# 4_cpu_control.net
KiCad netlist of a schematic drawn in EAGLE
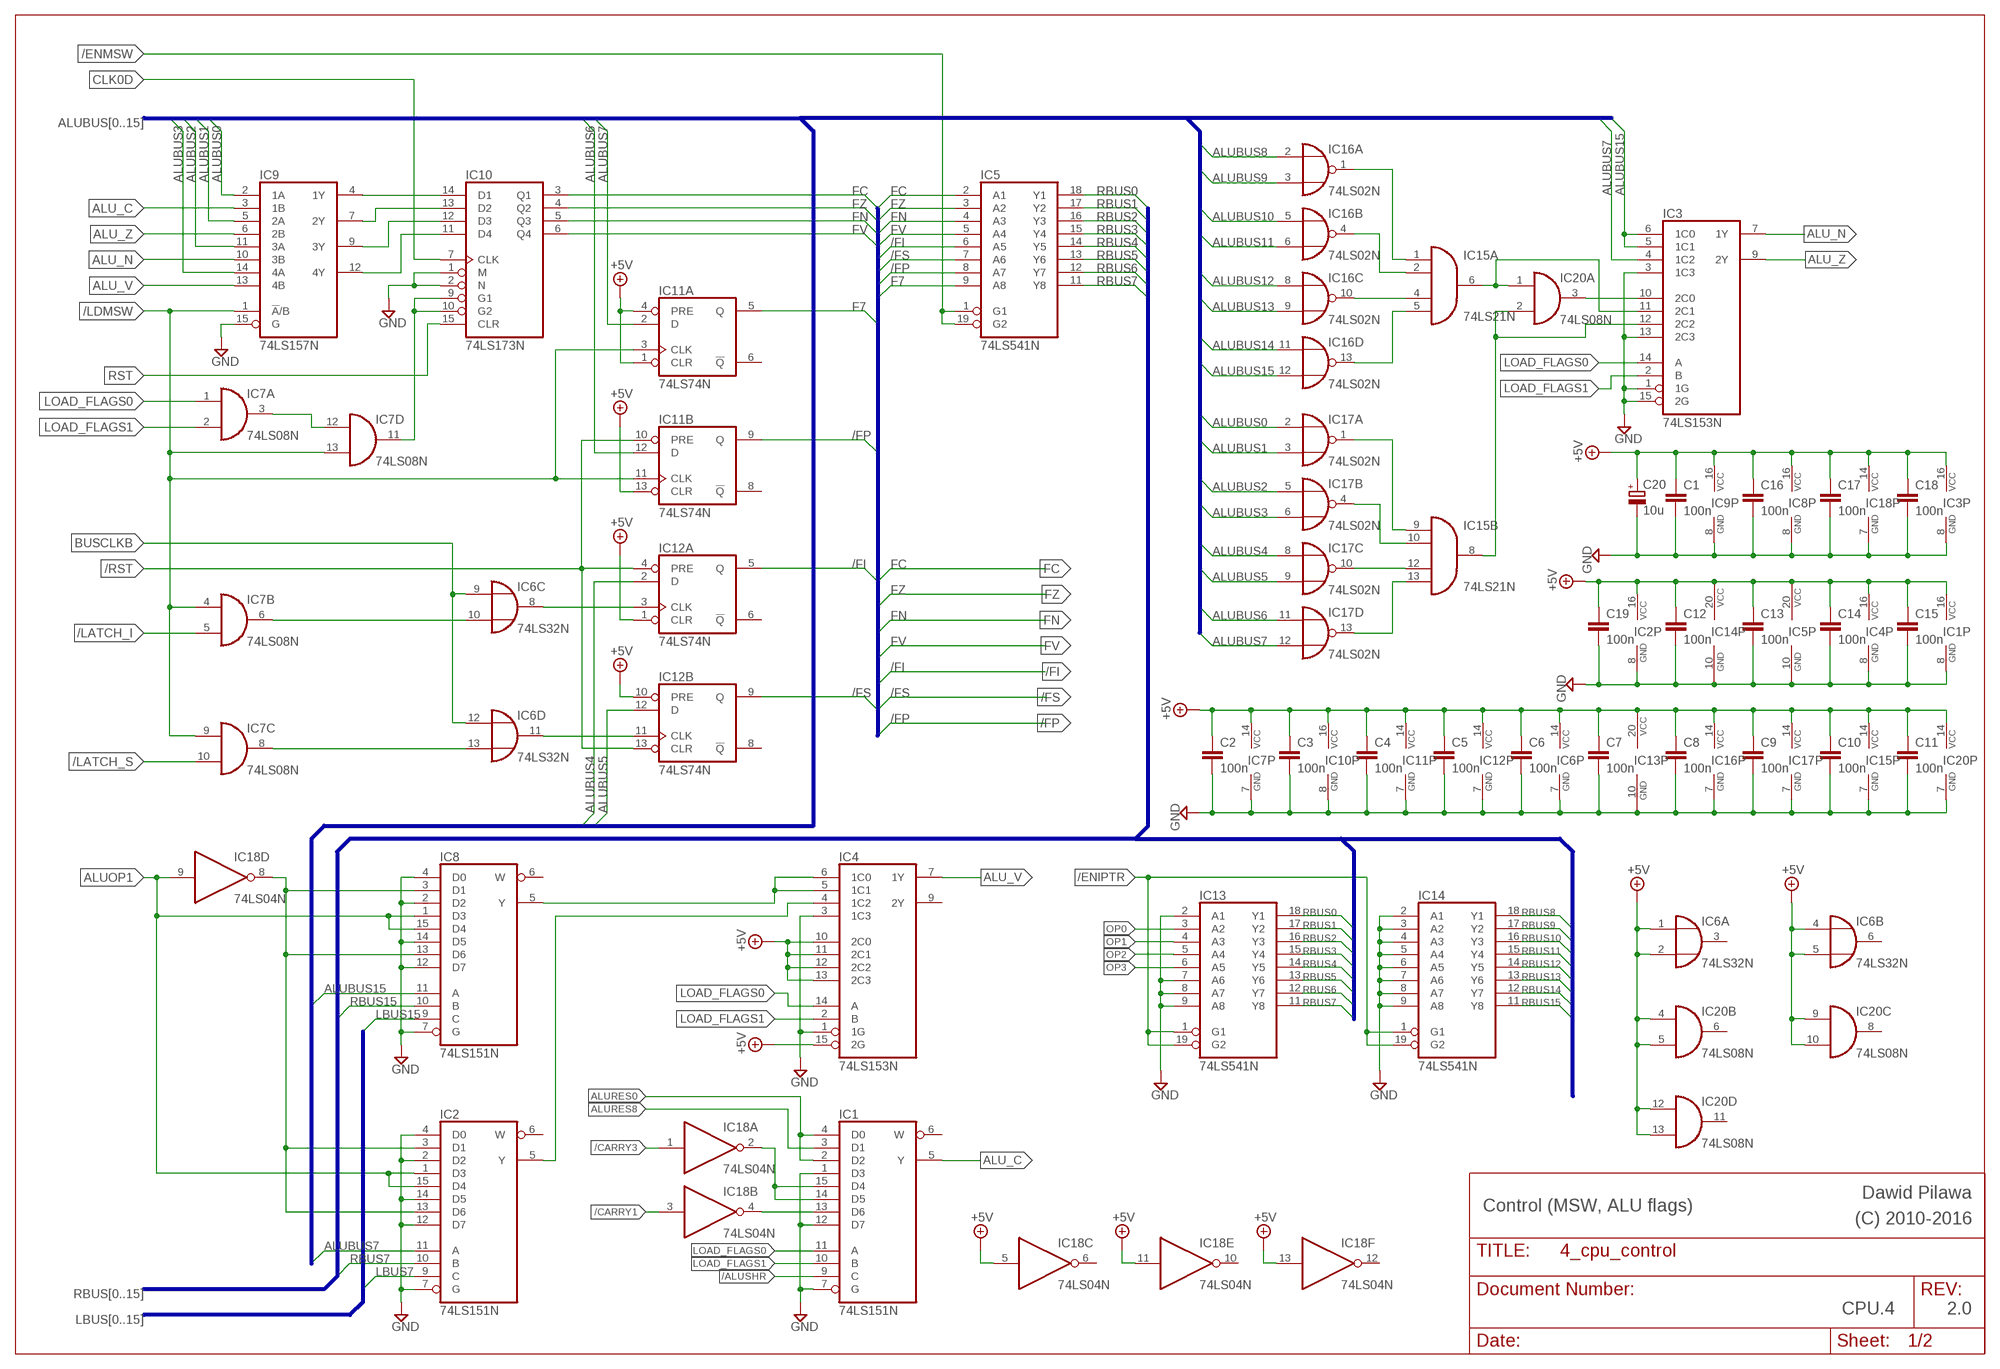
[diagram p0: schematic, sheet 1]
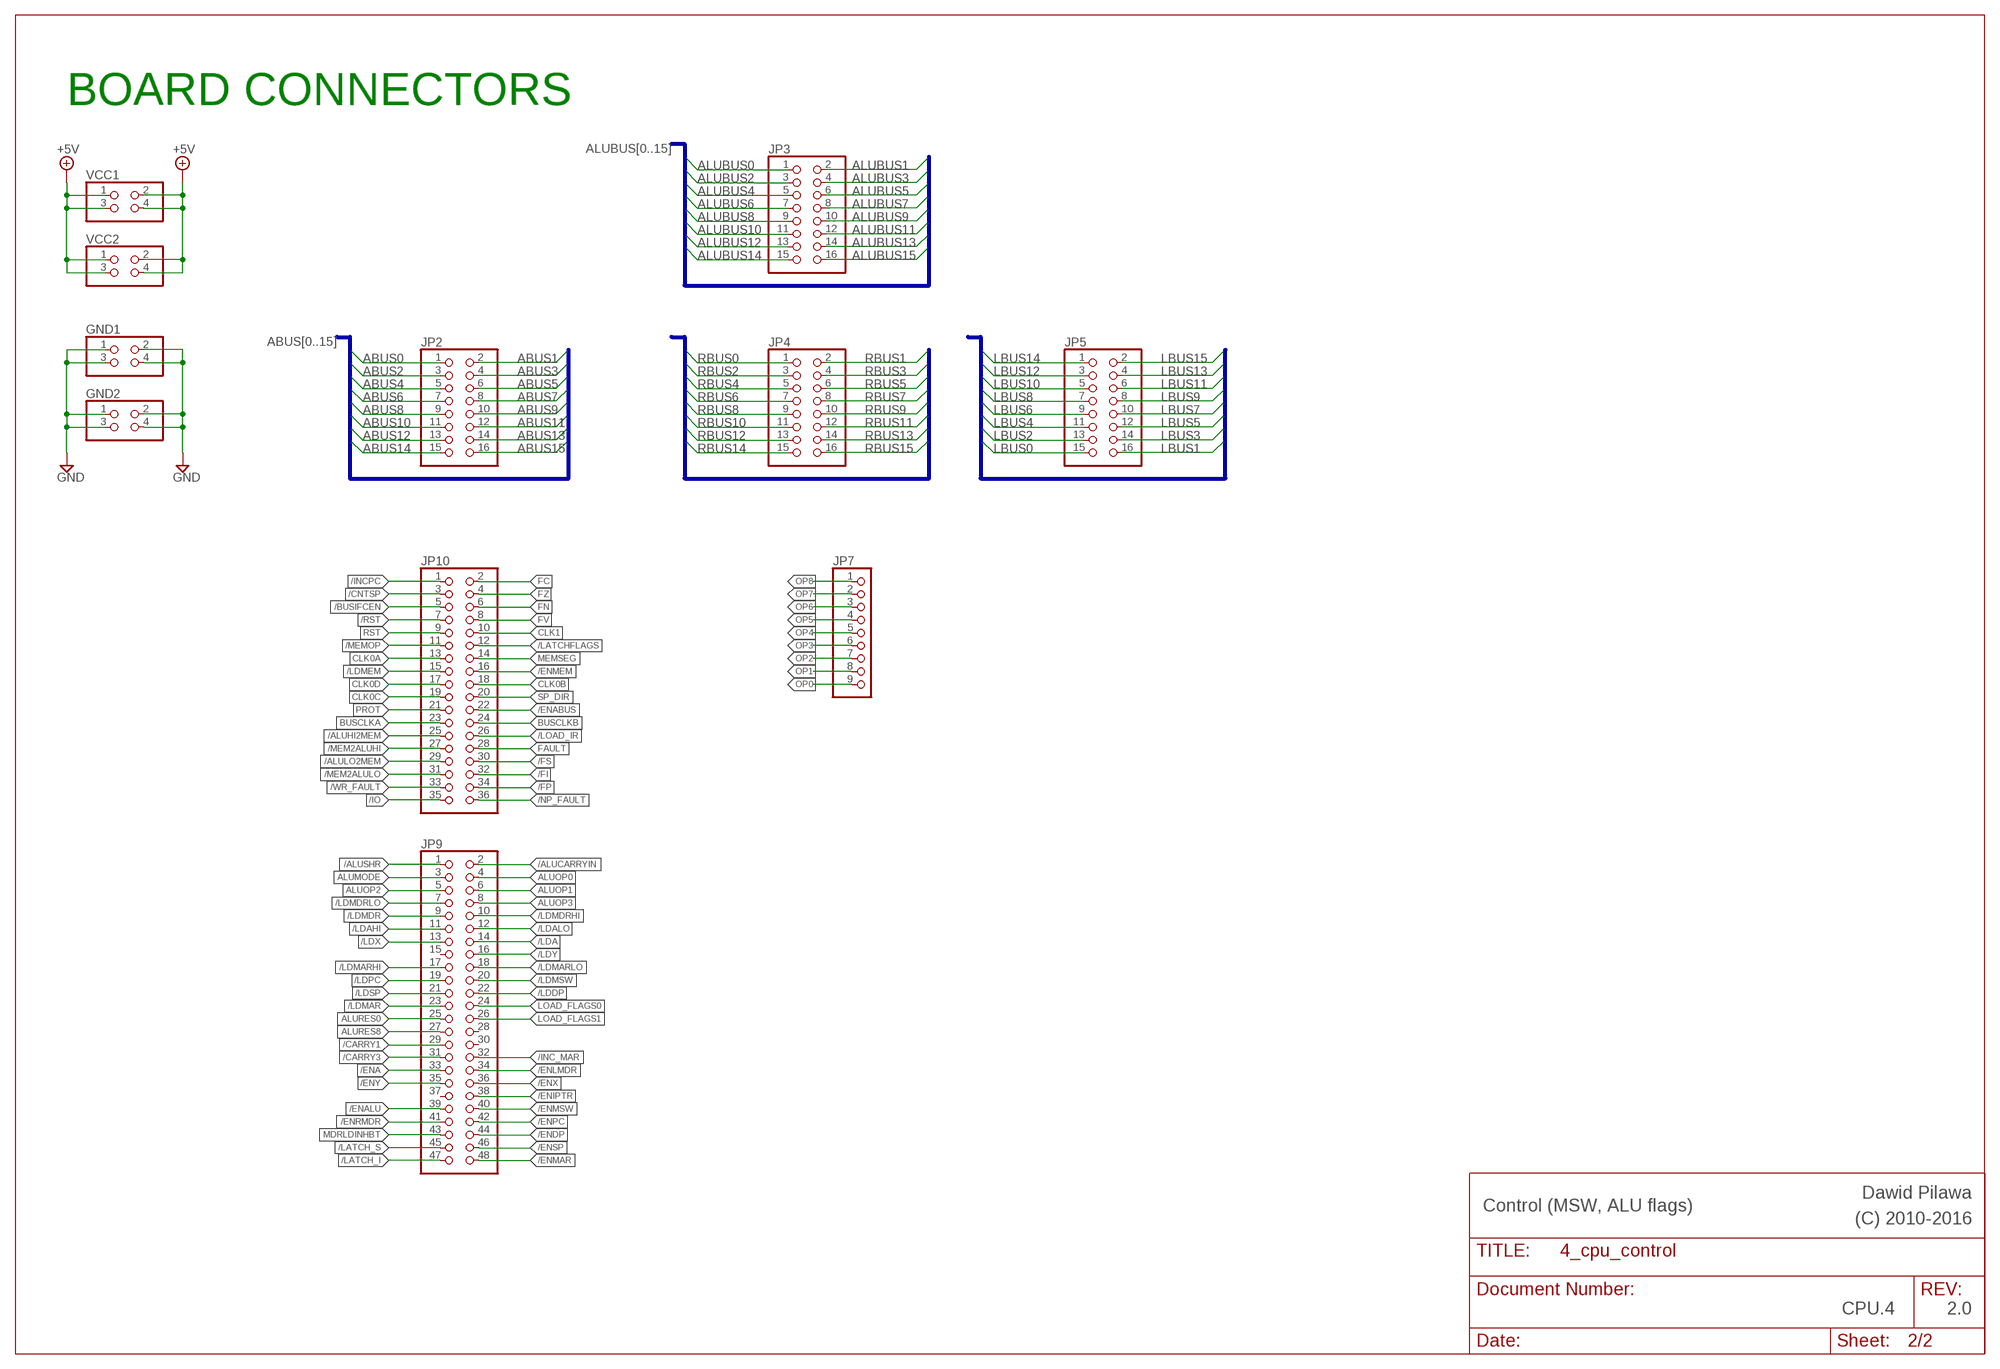
[diagram p1: schematic, sheet 2]

(export (version "E")
  (design (tool "Eeschema 10.0.6"))
  (components
    (comp (ref "GND1")
      (value "PINHD-2X2")
      (footprint "eagle-import:2X02")
      (libsource (lib "eagle-import") (part "PINHD-2X2"))
    )
    (comp (ref "GND2")
      (value "PINHD-2X2")
      (footprint "eagle-import:2X02")
      (libsource (lib "eagle-import") (part "PINHD-2X2"))
    )
    (comp (ref "JP2")
      (value "PINHD-2X8")
      (footprint "eagle-import:2X08")
      (libsource (lib "eagle-import") (part "PINHD-2X8"))
    )
    (comp (ref "JP3")
      (value "PINHD-2X8")
      (footprint "eagle-import:2X08")
      (libsource (lib "eagle-import") (part "PINHD-2X8"))
    )
    (comp (ref "JP4")
      (value "PINHD-2X8")
      (footprint "eagle-import:2X08")
      (libsource (lib "eagle-import") (part "PINHD-2X8"))
    )
    (comp (ref "JP5")
      (value "PINHD-2X8")
      (footprint "eagle-import:2X08")
      (libsource (lib "eagle-import") (part "PINHD-2X8"))
    )
    (comp (ref "JP7")
      (value "PINHD-1X9")
      (footprint "eagle-import:1X09")
      (libsource (lib "eagle-import") (part "PINHD-1X9"))
    )
    (comp (ref "JP9")
      (value "PINHD-2X24")
      (footprint "eagle-import:2X24")
      (libsource (lib "eagle-import") (part "PINHD-2X24"))
    )
    (comp (ref "JP10")
      (value "PINHD-2X18")
      (footprint "eagle-import:2X18")
      (libsource (lib "eagle-import") (part "PINHD-2X18"))
    )
    (comp (ref "VCC1")
      (value "PINHD-2X2")
      (footprint "eagle-import:2X02")
      (libsource (lib "eagle-import") (part "PINHD-2X2"))
    )
    (comp (ref "VCC2")
      (value "PINHD-2X2")
      (footprint "eagle-import:2X02")
      (libsource (lib "eagle-import") (part "PINHD-2X2"))
    )
    (comp (ref "C1")
      (value "100n")
      (footprint "eagle-import:C050-024X044")
      (libsource (lib "eagle-import") (part "C-EU050-024X044"))
    )
    (comp (ref "C2")
      (value "100n")
      (footprint "eagle-import:C050-024X044")
      (libsource (lib "eagle-import") (part "C-EU050-024X044"))
    )
    (comp (ref "C3")
      (value "100n")
      (footprint "eagle-import:C050-024X044")
      (libsource (lib "eagle-import") (part "C-EU050-024X044"))
    )
    (comp (ref "C4")
      (value "100n")
      (footprint "eagle-import:C050-024X044")
      (libsource (lib "eagle-import") (part "C-EU050-024X044"))
    )
    (comp (ref "C5")
      (value "100n")
      (footprint "eagle-import:C050-024X044")
      (libsource (lib "eagle-import") (part "C-EU050-024X044"))
    )
    (comp (ref "C6")
      (value "100n")
      (footprint "eagle-import:C050-024X044")
      (libsource (lib "eagle-import") (part "C-EU050-024X044"))
    )
    (comp (ref "C7")
      (value "100n")
      (footprint "eagle-import:C050-024X044")
      (libsource (lib "eagle-import") (part "C-EU050-024X044"))
    )
    (comp (ref "C8")
      (value "100n")
      (footprint "eagle-import:C050-024X044")
      (libsource (lib "eagle-import") (part "C-EU050-024X044"))
    )
    (comp (ref "C9")
      (value "100n")
      (footprint "eagle-import:C050-024X044")
      (libsource (lib "eagle-import") (part "C-EU050-024X044"))
    )
    (comp (ref "C10")
      (value "100n")
      (footprint "eagle-import:C050-024X044")
      (libsource (lib "eagle-import") (part "C-EU050-024X044"))
    )
    (comp (ref "C11")
      (value "100n")
      (footprint "eagle-import:C050-024X044")
      (libsource (lib "eagle-import") (part "C-EU050-024X044"))
    )
    (comp (ref "C12")
      (value "100n")
      (footprint "eagle-import:C050-024X044")
      (libsource (lib "eagle-import") (part "C-EU050-024X044"))
    )
    (comp (ref "C13")
      (value "100n")
      (footprint "eagle-import:C050-024X044")
      (libsource (lib "eagle-import") (part "C-EU050-024X044"))
    )
    (comp (ref "C14")
      (value "100n")
      (footprint "eagle-import:C050-024X044")
      (libsource (lib "eagle-import") (part "C-EU050-024X044"))
    )
    (comp (ref "C15")
      (value "100n")
      (footprint "eagle-import:C050-024X044")
      (libsource (lib "eagle-import") (part "C-EU050-024X044"))
    )
    (comp (ref "C16")
      (value "100n")
      (footprint "eagle-import:C050-024X044")
      (libsource (lib "eagle-import") (part "C-EU050-024X044"))
    )
    (comp (ref "C17")
      (value "100n")
      (footprint "eagle-import:C050-024X044")
      (libsource (lib "eagle-import") (part "C-EU050-024X044"))
    )
    (comp (ref "C18")
      (value "100n")
      (footprint "eagle-import:C050-024X044")
      (libsource (lib "eagle-import") (part "C-EU050-024X044"))
    )
    (comp (ref "C19")
      (value "100n")
      (footprint "eagle-import:C050-024X044")
      (libsource (lib "eagle-import") (part "C-EU050-024X044"))
    )
    (comp (ref "C20")
      (value "10u")
      (footprint "eagle-import:E2,5-6")
      (libsource (lib "eagle-import") (part "CPOL-EUE2.5-6"))
    )
    (comp (ref "IC1")
      (value "74LS151N")
      (footprint "eagle-import:DIL16")
      (libsource (lib "eagle-import") (part "74151NLS"))
    )
    (comp (ref "IC2")
      (value "74LS151N")
      (footprint "eagle-import:DIL16")
      (libsource (lib "eagle-import") (part "74151NLS"))
    )
    (comp (ref "IC3")
      (value "74LS153N")
      (footprint "eagle-import:DIL16")
      (libsource (lib "eagle-import") (part "74153NLS"))
    )
    (comp (ref "IC4")
      (value "74LS153N")
      (footprint "eagle-import:DIL16")
      (libsource (lib "eagle-import") (part "74153NLS"))
    )
    (comp (ref "IC5")
      (value "74LS541N")
      (footprint "eagle-import:DIL20")
      (libsource (lib "eagle-import") (part "74541NLS"))
    )
    (comp (ref "IC6")
      (value "74LS32N")
      (footprint "eagle-import:DIL14")
      (libsource (lib "eagle-import") (part "7432NLS"))
    )
    (comp (ref "IC7")
      (value "74LS08N")
      (footprint "eagle-import:DIL14")
      (libsource (lib "eagle-import") (part "7408NLS"))
    )
    (comp (ref "IC8")
      (value "74LS151N")
      (footprint "eagle-import:DIL16")
      (libsource (lib "eagle-import") (part "74151NLS"))
    )
    (comp (ref "IC9")
      (value "74LS157N")
      (footprint "eagle-import:DIL16")
      (libsource (lib "eagle-import") (part "74157NLS"))
    )
    (comp (ref "IC10")
      (value "74LS173N")
      (footprint "eagle-import:DIL16")
      (libsource (lib "eagle-import") (part "74173NLS"))
    )
    (comp (ref "IC11")
      (value "74LS74N")
      (footprint "eagle-import:DIL14")
      (libsource (lib "eagle-import") (part "7474NLS"))
    )
    (comp (ref "IC12")
      (value "74LS74N")
      (footprint "eagle-import:DIL14")
      (libsource (lib "eagle-import") (part "7474NLS"))
    )
    (comp (ref "IC13")
      (value "74LS541N")
      (footprint "eagle-import:DIL20")
      (libsource (lib "eagle-import") (part "74541NLS"))
    )
    (comp (ref "IC14")
      (value "74LS541N")
      (footprint "eagle-import:DIL20")
      (libsource (lib "eagle-import") (part "74541NLS"))
    )
    (comp (ref "IC15")
      (value "74LS21N")
      (footprint "eagle-import:DIL14")
      (libsource (lib "eagle-import") (part "7421NLS"))
    )
    (comp (ref "IC16")
      (value "74LS02N")
      (footprint "eagle-import:DIL14")
      (libsource (lib "eagle-import") (part "7402NLS"))
    )
    (comp (ref "IC17")
      (value "74LS02N")
      (footprint "eagle-import:DIL14")
      (libsource (lib "eagle-import") (part "7402NLS"))
    )
    (comp (ref "IC18")
      (value "74LS04N")
      (footprint "eagle-import:DIL14")
      (libsource (lib "eagle-import") (part "7404NLS"))
    )
    (comp (ref "IC20")
      (value "74LS08N")
      (footprint "eagle-import:DIL14")
      (libsource (lib "eagle-import") (part "7408NLS"))
    )
  )
  (nets
    (net (code "15") (name "+5V") (class "Default")
      (node (ref "C1") (pin "1") (pinfunction "1_1") (pintype "passive"))
      (node (ref "C10") (pin "1") (pinfunction "1_1") (pintype "passive"))
      (node (ref "C11") (pin "1") (pinfunction "1_1") (pintype "passive"))
      (node (ref "C12") (pin "1") (pinfunction "1_1") (pintype "passive"))
      (node (ref "C13") (pin "1") (pinfunction "1_1") (pintype "passive"))
      (node (ref "C14") (pin "1") (pinfunction "1_1") (pintype "passive"))
      (node (ref "C15") (pin "1") (pinfunction "1_1") (pintype "passive"))
      (node (ref "C16") (pin "1") (pinfunction "1_1") (pintype "passive"))
      (node (ref "C17") (pin "1") (pinfunction "1_1") (pintype "passive"))
      (node (ref "C18") (pin "1") (pinfunction "1_1") (pintype "passive"))
      (node (ref "C19") (pin "1") (pinfunction "1_1") (pintype "passive"))
      (node (ref "C2") (pin "1") (pinfunction "1_1") (pintype "passive"))
      (node (ref "C20") (pin "+") (pinfunction "+_+") (pintype "passive"))
      (node (ref "C3") (pin "1") (pinfunction "1_1") (pintype "passive"))
      (node (ref "C4") (pin "1") (pinfunction "1_1") (pintype "passive"))
      (node (ref "C5") (pin "1") (pinfunction "1_1") (pintype "passive"))
      (node (ref "C6") (pin "1") (pinfunction "1_1") (pintype "passive"))
      (node (ref "C7") (pin "1") (pinfunction "1_1") (pintype "passive"))
      (node (ref "C8") (pin "1") (pinfunction "1_1") (pintype "passive"))
      (node (ref "C9") (pin "1") (pinfunction "1_1") (pintype "passive"))
      (node (ref "IC1") (pin "16") (pinfunction "VCC_16") (pintype "power_in"))
      (node (ref "IC10") (pin "16") (pinfunction "VCC_16") (pintype "power_in"))
      (node (ref "IC11") (pin "1") (pinfunction "CLR_1") (pintype "input"))
      (node (ref "IC11") (pin "13") (pinfunction "CLR_13") (pintype "input"))
      (node (ref "IC11") (pin "14") (pinfunction "VCC_14") (pintype "power_in"))
      (node (ref "IC11") (pin "4") (pinfunction "PRE_4") (pintype "input"))
      (node (ref "IC12") (pin "1") (pinfunction "CLR_1") (pintype "input"))
      (node (ref "IC12") (pin "10") (pinfunction "PRE_10") (pintype "input"))
      (node (ref "IC12") (pin "14") (pinfunction "VCC_14") (pintype "power_in"))
      (node (ref "IC13") (pin "20") (pinfunction "VCC_20") (pintype "power_in"))
      (node (ref "IC14") (pin "20") (pinfunction "VCC_20") (pintype "power_in"))
      (node (ref "IC15") (pin "14") (pinfunction "VCC_14") (pintype "power_in"))
      (node (ref "IC16") (pin "14") (pinfunction "VCC_14") (pintype "power_in"))
      (node (ref "IC17") (pin "14") (pinfunction "VCC_14") (pintype "power_in"))
      (node (ref "IC18") (pin "11") (pinfunction "I_11") (pintype "input"))
      (node (ref "IC18") (pin "13") (pinfunction "I_13") (pintype "input"))
      (node (ref "IC18") (pin "14") (pinfunction "VCC_14") (pintype "power_in"))
      (node (ref "IC18") (pin "5") (pinfunction "I_5") (pintype "input"))
      (node (ref "IC2") (pin "16") (pinfunction "VCC_16") (pintype "power_in"))
      (node (ref "IC20") (pin "10") (pinfunction "I1_10") (pintype "input"))
      (node (ref "IC20") (pin "12") (pinfunction "I0_12") (pintype "input"))
      (node (ref "IC20") (pin "13") (pinfunction "I1_13") (pintype "input"))
      (node (ref "IC20") (pin "14") (pinfunction "VCC_14") (pintype "power_in"))
      (node (ref "IC20") (pin "4") (pinfunction "I0_4") (pintype "input"))
      (node (ref "IC20") (pin "5") (pinfunction "I1_5") (pintype "input"))
      (node (ref "IC20") (pin "9") (pinfunction "I0_9") (pintype "input"))
      (node (ref "IC3") (pin "16") (pinfunction "VCC_16") (pintype "power_in"))
      (node (ref "IC4") (pin "10") (pinfunction "2C0_10") (pintype "input"))
      (node (ref "IC4") (pin "11") (pinfunction "2C1_11") (pintype "input"))
      (node (ref "IC4") (pin "12") (pinfunction "2C2_12") (pintype "input"))
      (node (ref "IC4") (pin "13") (pinfunction "2C3_13") (pintype "input"))
      (node (ref "IC4") (pin "15") (pinfunction "2G_15") (pintype "input"))
      (node (ref "IC4") (pin "16") (pinfunction "VCC_16") (pintype "power_in"))
      (node (ref "IC5") (pin "20") (pinfunction "VCC_20") (pintype "power_in"))
      (node (ref "IC6") (pin "1") (pinfunction "I0_1") (pintype "input"))
      (node (ref "IC6") (pin "14") (pinfunction "VCC_14") (pintype "power_in"))
      (node (ref "IC6") (pin "2") (pinfunction "I1_2") (pintype "input"))
      (node (ref "IC6") (pin "4") (pinfunction "I0_4") (pintype "input"))
      (node (ref "IC6") (pin "5") (pinfunction "I1_5") (pintype "input"))
      (node (ref "IC7") (pin "14") (pinfunction "VCC_14") (pintype "power_in"))
      (node (ref "IC8") (pin "16") (pinfunction "VCC_16") (pintype "power_in"))
      (node (ref "IC9") (pin "16") (pinfunction "VCC_16") (pintype "power_in"))
      (node (ref "VCC1") (pin "1") (pinfunction "1_1") (pintype "passive"))
      (node (ref "VCC1") (pin "2") (pinfunction "2_2") (pintype "passive"))
      (node (ref "VCC1") (pin "3") (pinfunction "3_3") (pintype "passive"))
      (node (ref "VCC1") (pin "4") (pinfunction "4_4") (pintype "passive"))
      (node (ref "VCC2") (pin "1") (pinfunction "1_1") (pintype "passive"))
      (node (ref "VCC2") (pin "2") (pinfunction "2_2") (pintype "passive"))
      (node (ref "VCC2") (pin "3") (pinfunction "3_3") (pintype "passive"))
      (node (ref "VCC2") (pin "4") (pinfunction "4_4") (pintype "passive"))
    )
    (net (code "21") (name "ABUS0") (class "Default")
      (node (ref "JP2") (pin "1") (pinfunction "1_1") (pintype "passive"))
    )
    (net (code "22") (name "ABUS1") (class "Default")
      (node (ref "JP2") (pin "2") (pinfunction "2_2") (pintype "passive"))
    )
    (net (code "23") (name "ABUS2") (class "Default")
      (node (ref "JP2") (pin "3") (pinfunction "3_3") (pintype "passive"))
    )
    (net (code "24") (name "ABUS3") (class "Default")
      (node (ref "JP2") (pin "4") (pinfunction "4_4") (pintype "passive"))
    )
    (net (code "25") (name "ABUS4") (class "Default")
      (node (ref "JP2") (pin "5") (pinfunction "5_5") (pintype "passive"))
    )
    (net (code "26") (name "ABUS5") (class "Default")
      (node (ref "JP2") (pin "6") (pinfunction "6_6") (pintype "passive"))
    )
    (net (code "27") (name "ABUS6") (class "Default")
      (node (ref "JP2") (pin "7") (pinfunction "7_7") (pintype "passive"))
    )
    (net (code "28") (name "ABUS7") (class "Default")
      (node (ref "JP2") (pin "8") (pinfunction "8_8") (pintype "passive"))
    )
    (net (code "29") (name "ABUS8") (class "Default")
      (node (ref "JP2") (pin "9") (pinfunction "9_9") (pintype "passive"))
    )
    (net (code "30") (name "ABUS9") (class "Default")
      (node (ref "JP2") (pin "10") (pinfunction "10_10") (pintype "passive"))
    )
    (net (code "31") (name "ABUS10") (class "Default")
      (node (ref "JP2") (pin "11") (pinfunction "11_11") (pintype "passive"))
    )
    (net (code "32") (name "ABUS11") (class "Default")
      (node (ref "JP2") (pin "12") (pinfunction "12_12") (pintype "passive"))
    )
    (net (code "33") (name "ABUS12") (class "Default")
      (node (ref "JP2") (pin "13") (pinfunction "13_13") (pintype "passive"))
    )
    (net (code "34") (name "ABUS13") (class "Default")
      (node (ref "JP2") (pin "14") (pinfunction "14_14") (pintype "passive"))
    )
    (net (code "35") (name "ABUS14") (class "Default")
      (node (ref "JP2") (pin "15") (pinfunction "15_15") (pintype "passive"))
    )
    (net (code "36") (name "ABUS15") (class "Default")
      (node (ref "JP2") (pin "16") (pinfunction "16_16") (pintype "passive"))
    )
    (net (code "37") (name "ALUBUS0") (class "Default")
      (node (ref "IC17") (pin "2") (pinfunction "I0_2") (pintype "input"))
      (node (ref "IC9") (pin "2") (pinfunction "1A_2") (pintype "input"))
      (node (ref "JP3") (pin "1") (pinfunction "1_1") (pintype "passive"))
    )
    (net (code "38") (name "ALUBUS1") (class "Default")
      (node (ref "IC17") (pin "3") (pinfunction "I1_3") (pintype "input"))
      (node (ref "IC9") (pin "5") (pinfunction "2A_5") (pintype "input"))
      (node (ref "JP3") (pin "2") (pinfunction "2_2") (pintype "passive"))
    )
    (net (code "39") (name "ALUBUS2") (class "Default")
      (node (ref "IC17") (pin "5") (pinfunction "I0_5") (pintype "input"))
      (node (ref "IC9") (pin "11") (pinfunction "3A_11") (pintype "input"))
      (node (ref "JP3") (pin "3") (pinfunction "3_3") (pintype "passive"))
    )
    (net (code "40") (name "ALUBUS3") (class "Default")
      (node (ref "IC17") (pin "6") (pinfunction "I1_6") (pintype "input"))
      (node (ref "IC9") (pin "14") (pinfunction "4A_14") (pintype "input"))
      (node (ref "JP3") (pin "4") (pinfunction "4_4") (pintype "passive"))
    )
    (net (code "41") (name "ALUBUS4") (class "Default")
      (node (ref "IC12") (pin "2") (pinfunction "D_2") (pintype "input"))
      (node (ref "IC17") (pin "8") (pinfunction "I0_8") (pintype "input"))
      (node (ref "JP3") (pin "5") (pinfunction "5_5") (pintype "passive"))
    )
    (net (code "42") (name "ALUBUS5") (class "Default")
      (node (ref "IC12") (pin "12") (pinfunction "D_12") (pintype "input"))
      (node (ref "IC17") (pin "9") (pinfunction "I1_9") (pintype "input"))
      (node (ref "JP3") (pin "6") (pinfunction "6_6") (pintype "passive"))
    )
    (net (code "43") (name "ALUBUS6") (class "Default")
      (node (ref "IC11") (pin "12") (pinfunction "D_12") (pintype "input"))
      (node (ref "IC17") (pin "11") (pinfunction "I0_11") (pintype "input"))
      (node (ref "JP3") (pin "7") (pinfunction "7_7") (pintype "passive"))
    )
    (net (code "44") (name "ALUBUS7") (class "Default")
      (node (ref "IC11") (pin "2") (pinfunction "D_2") (pintype "input"))
      (node (ref "IC17") (pin "12") (pinfunction "I1_12") (pintype "input"))
      (node (ref "IC2") (pin "11") (pinfunction "A_11") (pintype "input"))
      (node (ref "IC3") (pin "4") (pinfunction "1C2_4") (pintype "input"))
      (node (ref "JP3") (pin "8") (pinfunction "8_8") (pintype "passive"))
    )
    (net (code "45") (name "ALUBUS8") (class "Default")
      (node (ref "IC16") (pin "2") (pinfunction "I0_2") (pintype "input"))
      (node (ref "JP3") (pin "9") (pinfunction "9_9") (pintype "passive"))
    )
    (net (code "46") (name "ALUBUS9") (class "Default")
      (node (ref "IC16") (pin "3") (pinfunction "I1_3") (pintype "input"))
      (node (ref "JP3") (pin "10") (pinfunction "10_10") (pintype "passive"))
    )
    (net (code "47") (name "ALUBUS10") (class "Default")
      (node (ref "IC16") (pin "5") (pinfunction "I0_5") (pintype "input"))
      (node (ref "JP3") (pin "11") (pinfunction "11_11") (pintype "passive"))
    )
    (net (code "48") (name "ALUBUS11") (class "Default")
      (node (ref "IC16") (pin "6") (pinfunction "I1_6") (pintype "input"))
      (node (ref "JP3") (pin "12") (pinfunction "12_12") (pintype "passive"))
    )
    (net (code "49") (name "ALUBUS12") (class "Default")
      (node (ref "IC16") (pin "8") (pinfunction "I0_8") (pintype "input"))
      (node (ref "JP3") (pin "13") (pinfunction "13_13") (pintype "passive"))
    )
    (net (code "50") (name "ALUBUS13") (class "Default")
      (node (ref "IC16") (pin "9") (pinfunction "I1_9") (pintype "input"))
      (node (ref "JP3") (pin "14") (pinfunction "14_14") (pintype "passive"))
    )
    (net (code "51") (name "ALUBUS14") (class "Default")
      (node (ref "IC16") (pin "11") (pinfunction "I0_11") (pintype "input"))
      (node (ref "JP3") (pin "15") (pinfunction "15_15") (pintype "passive"))
    )
    (net (code "52") (name "ALUBUS15") (class "Default")
      (node (ref "IC16") (pin "12") (pinfunction "I1_12") (pintype "input"))
      (node (ref "IC3") (pin "5") (pinfunction "1C1_5") (pintype "input"))
      (node (ref "IC3") (pin "6") (pinfunction "1C0_6") (pintype "input"))
      (node (ref "IC8") (pin "11") (pinfunction "A_11") (pintype "input"))
      (node (ref "JP3") (pin "16") (pinfunction "16_16") (pintype "passive"))
    )
    (net (code "53") (name "ALUMODE") (class "Default")
      (node (ref "JP9") (pin "3") (pinfunction "3_3") (pintype "passive"))
    )
    (net (code "54") (name "ALUOP0") (class "Default")
      (node (ref "JP9") (pin "4") (pinfunction "4_4") (pintype "passive"))
    )
    (net (code "55") (name "ALUOP1") (class "Default")
      (node (ref "IC18") (pin "9") (pinfunction "I_9") (pintype "input"))
      (node (ref "IC2") (pin "1") (pinfunction "D3_1") (pintype "input"))
      (node (ref "IC2") (pin "15") (pinfunction "D4_15") (pintype "input"))
      (node (ref "IC8") (pin "1") (pinfunction "D3_1") (pintype "input"))
      (node (ref "IC8") (pin "15") (pinfunction "D4_15") (pintype "input"))
      (node (ref "JP9") (pin "6") (pinfunction "6_6") (pintype "passive"))
    )
    (net (code "56") (name "ALUOP2") (class "Default")
      (node (ref "JP9") (pin "5") (pinfunction "5_5") (pintype "passive"))
    )
    (net (code "57") (name "ALUOP3") (class "Default")
      (node (ref "JP9") (pin "8") (pinfunction "8_8") (pintype "passive"))
    )
    (net (code "58") (name "ALURES0") (class "Default")
      (node (ref "IC1") (pin "2") (pinfunction "D2_2") (pintype "input"))
      (node (ref "IC1") (pin "4") (pinfunction "D0_4") (pintype "input"))
      (node (ref "JP9") (pin "25") (pinfunction "25_25") (pintype "passive"))
    )
    (net (code "59") (name "ALURES8") (class "Default")
      (node (ref "IC1") (pin "3") (pinfunction "D1_3") (pintype "input"))
      (node (ref "JP9") (pin "27") (pinfunction "27_27") (pintype "passive"))
    )
    (net (code "60") (name "ALU_C") (class "Default")
      (node (ref "IC1") (pin "5") (pinfunction "Y_5") (pintype "output"))
      (node (ref "IC9") (pin "3") (pinfunction "1B_3") (pintype "input"))
    )
    (net (code "61") (name "ALU_N") (class "Default")
      (node (ref "IC3") (pin "7") (pinfunction "1Y_7") (pintype "output"))
      (node (ref "IC9") (pin "10") (pinfunction "3B_10") (pintype "input"))
    )
    (net (code "62") (name "ALU_V") (class "Default")
      (node (ref "IC4") (pin "7") (pinfunction "1Y_7") (pintype "output"))
      (node (ref "IC9") (pin "13") (pinfunction "4B_13") (pintype "input"))
    )
    (net (code "63") (name "ALU_Z") (class "Default")
      (node (ref "IC3") (pin "9") (pinfunction "2Y_9") (pintype "output"))
      (node (ref "IC9") (pin "6") (pinfunction "2B_6") (pintype "input"))
    )
    (net (code "64") (name "BUSCLKA") (class "Default")
      (node (ref "JP10") (pin "23") (pinfunction "23_23") (pintype "passive"))
    )
    (net (code "65") (name "BUSCLKB") (class "Default")
      (node (ref "IC6") (pin "12") (pinfunction "I0_12") (pintype "input"))
      (node (ref "IC6") (pin "9") (pinfunction "I0_9") (pintype "input"))
      (node (ref "JP10") (pin "24") (pinfunction "24_24") (pintype "passive"))
    )
    (net (code "66") (name "CLK0A") (class "Default")
      (node (ref "JP10") (pin "13") (pinfunction "13_13") (pintype "passive"))
    )
    (net (code "67") (name "CLK0B") (class "Default")
      (node (ref "JP10") (pin "18") (pinfunction "18_18") (pintype "passive"))
    )
    (net (code "68") (name "CLK0C") (class "Default")
      (node (ref "JP10") (pin "19") (pinfunction "19_19") (pintype "passive"))
    )
    (net (code "69") (name "CLK0D") (class "Default")
      (node (ref "IC10") (pin "7") (pinfunction "CLK_7") (pintype "input"))
      (node (ref "JP10") (pin "17") (pinfunction "17_17") (pintype "passive"))
    )
    (net (code "70") (name "CLK1") (class "Default")
      (node (ref "JP10") (pin "10") (pinfunction "10_10") (pintype "passive"))
    )
    (net (code "71") (name "F7") (class "Default")
      (node (ref "IC11") (pin "5") (pinfunction "Q_5") (pintype "output"))
      (node (ref "IC5") (pin "9") (pinfunction "A8_9") (pintype "input"))
    )
    (net (code "72") (name "FAULT") (class "Default")
      (node (ref "JP10") (pin "28") (pinfunction "28_28") (pintype "passive"))
    )
    (net (code "73") (name "FC") (class "Default")
      (node (ref "IC10") (pin "3") (pinfunction "Q1_3") (pintype "tri_state"))
      (node (ref "IC5") (pin "2") (pinfunction "A1_2") (pintype "input"))
      (node (ref "JP10") (pin "2") (pinfunction "2_2") (pintype "passive"))
    )
    (net (code "74") (name "FN") (class "Default")
      (node (ref "IC10") (pin "5") (pinfunction "Q3_5") (pintype "tri_state"))
      (node (ref "IC5") (pin "4") (pinfunction "A3_4") (pintype "input"))
      (node (ref "JP10") (pin "6") (pinfunction "6_6") (pintype "passive"))
    )
    (net (code "75") (name "FV") (class "Default")
      (node (ref "IC10") (pin "6") (pinfunction "Q4_6") (pintype "tri_state"))
      (node (ref "IC5") (pin "5") (pinfunction "A4_5") (pintype "input"))
      (node (ref "JP10") (pin "8") (pinfunction "8_8") (pintype "passive"))
    )
    (net (code "76") (name "FZ") (class "Default")
      (node (ref "IC10") (pin "4") (pinfunction "Q2_4") (pintype "tri_state"))
      (node (ref "IC5") (pin "3") (pinfunction "A2_3") (pintype "input"))
      (node (ref "JP10") (pin "4") (pinfunction "4_4") (pintype "passive"))
    )
    (net (code "77") (name "GND") (class "Default")
      (node (ref "C1") (pin "2") (pinfunction "2_2") (pintype "passive"))
      (node (ref "C10") (pin "2") (pinfunction "2_2") (pintype "passive"))
      (node (ref "C11") (pin "2") (pinfunction "2_2") (pintype "passive"))
      (node (ref "C12") (pin "2") (pinfunction "2_2") (pintype "passive"))
      (node (ref "C13") (pin "2") (pinfunction "2_2") (pintype "passive"))
      (node (ref "C14") (pin "2") (pinfunction "2_2") (pintype "passive"))
      (node (ref "C15") (pin "2") (pinfunction "2_2") (pintype "passive"))
      (node (ref "C16") (pin "2") (pinfunction "2_2") (pintype "passive"))
      (node (ref "C17") (pin "2") (pinfunction "2_2") (pintype "passive"))
      (node (ref "C18") (pin "2") (pinfunction "2_2") (pintype "passive"))
      (node (ref "C19") (pin "2") (pinfunction "2_2") (pintype "passive"))
      (node (ref "C2") (pin "2") (pinfunction "2_2") (pintype "passive"))
      (node (ref "C20") (pin "-") (pinfunction "-_-") (pintype "passive"))
      (node (ref "C3") (pin "2") (pinfunction "2_2") (pintype "passive"))
      (node (ref "C4") (pin "2") (pinfunction "2_2") (pintype "passive"))
      (node (ref "C5") (pin "2") (pinfunction "2_2") (pintype "passive"))
      (node (ref "C6") (pin "2") (pinfunction "2_2") (pintype "passive"))
      (node (ref "C7") (pin "2") (pinfunction "2_2") (pintype "passive"))
      (node (ref "C8") (pin "2") (pinfunction "2_2") (pintype "passive"))
      (node (ref "C9") (pin "2") (pinfunction "2_2") (pintype "passive"))
      (node (ref "GND1") (pin "1") (pinfunction "1_1") (pintype "passive"))
      (node (ref "GND1") (pin "2") (pinfunction "2_2") (pintype "passive"))
      (node (ref "GND1") (pin "3") (pinfunction "3_3") (pintype "passive"))
      (node (ref "GND1") (pin "4") (pinfunction "4_4") (pintype "passive"))
      (node (ref "GND2") (pin "1") (pinfunction "1_1") (pintype "passive"))
      (node (ref "GND2") (pin "2") (pinfunction "2_2") (pintype "passive"))
      (node (ref "GND2") (pin "3") (pinfunction "3_3") (pintype "passive"))
      (node (ref "GND2") (pin "4") (pinfunction "4_4") (pintype "passive"))
      (node (ref "IC1") (pin "1") (pinfunction "D3_1") (pintype "input"))
      (node (ref "IC1") (pin "12") (pinfunction "D7_12") (pintype "input"))
      (node (ref "IC1") (pin "7") (pinfunction "G_7") (pintype "input"))
      (node (ref "IC1") (pin "8") (pinfunction "GND_8") (pintype "power_in"))
      (node (ref "IC10") (pin "1") (pinfunction "M_1") (pintype "input"))
      (node (ref "IC10") (pin "2") (pinfunction "N_2") (pintype "input"))
      (node (ref "IC10") (pin "8") (pinfunction "GND_8") (pintype "power_in"))
      (node (ref "IC11") (pin "7") (pinfunction "GND_7") (pintype "power_in"))
      (node (ref "IC12") (pin "7") (pinfunction "GND_7") (pintype "power_in"))
      (node (ref "IC13") (pin "10") (pinfunction "GND_10") (pintype "power_in"))
      (node (ref "IC13") (pin "2") (pinfunction "A1_2") (pintype "input"))
      (node (ref "IC13") (pin "7") (pinfunction "A6_7") (pintype "input"))
      (node (ref "IC13") (pin "8") (pinfunction "A7_8") (pintype "input"))
      (node (ref "IC13") (pin "9") (pinfunction "A8_9") (pintype "input"))
      (node (ref "IC14") (pin "10") (pinfunction "GND_10") (pintype "power_in"))
      (node (ref "IC14") (pin "2") (pinfunction "A1_2") (pintype "input"))
      (node (ref "IC14") (pin "3") (pinfunction "A2_3") (pintype "input"))
      (node (ref "IC14") (pin "4") (pinfunction "A3_4") (pintype "input"))
      (node (ref "IC14") (pin "5") (pinfunction "A4_5") (pintype "input"))
      (node (ref "IC14") (pin "6") (pinfunction "A5_6") (pintype "input"))
      (node (ref "IC14") (pin "7") (pinfunction "A6_7") (pintype "input"))
      (node (ref "IC14") (pin "8") (pinfunction "A7_8") (pintype "input"))
      (node (ref "IC14") (pin "9") (pinfunction "A8_9") (pintype "input"))
      (node (ref "IC15") (pin "7") (pinfunction "GND_7") (pintype "power_in"))
      (node (ref "IC16") (pin "7") (pinfunction "GND_7") (pintype "power_in"))
      (node (ref "IC17") (pin "7") (pinfunction "GND_7") (pintype "power_in"))
      (node (ref "IC18") (pin "7") (pinfunction "GND_7") (pintype "power_in"))
      (node (ref "IC2") (pin "12") (pinfunction "D7_12") (pintype "input"))
      (node (ref "IC2") (pin "14") (pinfunction "D5_14") (pintype "input"))
      (node (ref "IC2") (pin "2") (pinfunction "D2_2") (pintype "input"))
      (node (ref "IC2") (pin "4") (pinfunction "D0_4") (pintype "input"))
      (node (ref "IC2") (pin "7") (pinfunction "G_7") (pintype "input"))
      (node (ref "IC2") (pin "8") (pinfunction "GND_8") (pintype "power_in"))
      (node (ref "IC20") (pin "7") (pinfunction "GND_7") (pintype "power_in"))
      (node (ref "IC3") (pin "1") (pinfunction "1G_1") (pintype "input"))
      (node (ref "IC3") (pin "13") (pinfunction "2C3_13") (pintype "input"))
      (node (ref "IC3") (pin "15") (pinfunction "2G_15") (pintype "input"))
      (node (ref "IC3") (pin "3") (pinfunction "1C3_3") (pintype "input"))
      (node (ref "IC3") (pin "8") (pinfunction "GND_8") (pintype "power_in"))
      (node (ref "IC4") (pin "1") (pinfunction "1G_1") (pintype "input"))
      (node (ref "IC4") (pin "3") (pinfunction "1C3_3") (pintype "input"))
      (node (ref "IC4") (pin "8") (pinfunction "GND_8") (pintype "power_in"))
      (node (ref "IC5") (pin "10") (pinfunction "GND_10") (pintype "power_in"))
      (node (ref "IC6") (pin "7") (pinfunction "GND_7") (pintype "power_in"))
      (node (ref "IC7") (pin "7") (pinfunction "GND_7") (pintype "power_in"))
      (node (ref "IC8") (pin "12") (pinfunction "D7_12") (pintype "input"))
      (node (ref "IC8") (pin "14") (pinfunction "D5_14") (pintype "input"))
      (node (ref "IC8") (pin "2") (pinfunction "D2_2") (pintype "input"))
      (node (ref "IC8") (pin "4") (pinfunction "D0_4") (pintype "input"))
      (node (ref "IC8") (pin "7") (pinfunction "G_7") (pintype "input"))
      (node (ref "IC8") (pin "8") (pinfunction "GND_8") (pintype "power_in"))
      (node (ref "IC9") (pin "15") (pinfunction "G_15") (pintype "input"))
      (node (ref "IC9") (pin "8") (pinfunction "GND_8") (pintype "power_in"))
    )
    (net (code "78") (name "LBUS0") (class "Default")
      (node (ref "JP5") (pin "15") (pinfunction "15_15") (pintype "passive"))
    )
    (net (code "79") (name "LBUS1") (class "Default")
      (node (ref "JP5") (pin "16") (pinfunction "16_16") (pintype "passive"))
    )
    (net (code "80") (name "LBUS2") (class "Default")
      (node (ref "JP5") (pin "13") (pinfunction "13_13") (pintype "passive"))
    )
    (net (code "81") (name "LBUS3") (class "Default")
      (node (ref "JP5") (pin "14") (pinfunction "14_14") (pintype "passive"))
    )
    (net (code "82") (name "LBUS4") (class "Default")
      (node (ref "JP5") (pin "11") (pinfunction "11_11") (pintype "passive"))
    )
    (net (code "83") (name "LBUS5") (class "Default")
      (node (ref "JP5") (pin "12") (pinfunction "12_12") (pintype "passive"))
    )
    (net (code "84") (name "LBUS6") (class "Default")
      (node (ref "JP5") (pin "9") (pinfunction "9_9") (pintype "passive"))
    )
    (net (code "85") (name "LBUS7") (class "Default")
      (node (ref "IC2") (pin "9") (pinfunction "C_9") (pintype "input"))
      (node (ref "JP5") (pin "10") (pinfunction "10_10") (pintype "passive"))
    )
    (net (code "86") (name "LBUS8") (class "Default")
      (node (ref "JP5") (pin "7") (pinfunction "7_7") (pintype "passive"))
    )
    (net (code "87") (name "LBUS9") (class "Default")
      (node (ref "JP5") (pin "8") (pinfunction "8_8") (pintype "passive"))
    )
    (net (code "88") (name "LBUS10") (class "Default")
      (node (ref "JP5") (pin "5") (pinfunction "5_5") (pintype "passive"))
    )
    (net (code "89") (name "LBUS11") (class "Default")
      (node (ref "JP5") (pin "6") (pinfunction "6_6") (pintype "passive"))
    )
    (net (code "90") (name "LBUS12") (class "Default")
      (node (ref "JP5") (pin "3") (pinfunction "3_3") (pintype "passive"))
    )
    (net (code "91") (name "LBUS13") (class "Default")
      (node (ref "JP5") (pin "4") (pinfunction "4_4") (pintype "passive"))
    )
    (net (code "92") (name "LBUS14") (class "Default")
      (node (ref "JP5") (pin "1") (pinfunction "1_1") (pintype "passive"))
    )
    (net (code "93") (name "LBUS15") (class "Default")
      (node (ref "IC8") (pin "9") (pinfunction "C_9") (pintype "input"))
      (node (ref "JP5") (pin "2") (pinfunction "2_2") (pintype "passive"))
    )
    (net (code "94") (name "LOAD_FLAGS0") (class "Default")
      (node (ref "IC1") (pin "11") (pinfunction "A_11") (pintype "input"))
      (node (ref "IC3") (pin "14") (pinfunction "A_14") (pintype "input"))
      (node (ref "IC4") (pin "14") (pinfunction "A_14") (pintype "input"))
      (node (ref "IC7") (pin "1") (pinfunction "I0_1") (pintype "input"))
      (node (ref "JP9") (pin "24") (pinfunction "24_24") (pintype "passive"))
    )
    (net (code "95") (name "LOAD_FLAGS1") (class "Default")
      (node (ref "IC1") (pin "10") (pinfunction "B_10") (pintype "input"))
      (node (ref "IC3") (pin "2") (pinfunction "B_2") (pintype "input"))
      (node (ref "IC4") (pin "2") (pinfunction "B_2") (pintype "input"))
      (node (ref "IC7") (pin "2") (pinfunction "I1_2") (pintype "input"))
      (node (ref "JP9") (pin "26") (pinfunction "26_26") (pintype "passive"))
    )
    (net (code "96") (name "MDRLDINHBT") (class "Default")
      (node (ref "JP9") (pin "43") (pinfunction "43_43") (pintype "passive"))
    )
    (net (code "97") (name "MEMSEG") (class "Default")
      (node (ref "JP10") (pin "14") (pinfunction "14_14") (pintype "passive"))
    )
    (net (code "98") (name "Net-(IC2A-Y)") (class "Default")
      (node (ref "IC2") (pin "5") (pinfunction "Y_5") (pintype "output"))
      (node (ref "IC4") (pin "4") (pinfunction "1C2_4") (pintype "input"))
    )
    (net (code "99") (name "Net-(IC4A-1C0)") (class "Default")
      (node (ref "IC4") (pin "5") (pinfunction "1C1_5") (pintype "input"))
      (node (ref "IC4") (pin "6") (pinfunction "1C0_6") (pintype "input"))
      (node (ref "IC8") (pin "5") (pinfunction "Y_5") (pintype "output"))
    )
    (net (code "100") (name "Net-(IC6C-I1)") (class "Default")
      (node (ref "IC6") (pin "10") (pinfunction "I1_10") (pintype "input"))
      (node (ref "IC7") (pin "6") (pinfunction "O_6") (pintype "output"))
    )
    (net (code "101") (name "Net-(IC6D-I1)") (class "Default")
      (node (ref "IC6") (pin "13") (pinfunction "I1_13") (pintype "input"))
      (node (ref "IC7") (pin "8") (pinfunction "O_8") (pintype "output"))
    )
    (net (code "102") (name "Net-(IC7A-O)") (class "Default")
      (node (ref "IC7") (pin "12") (pinfunction "I0_12") (pintype "input"))
      (node (ref "IC7") (pin "3") (pinfunction "O_3") (pintype "output"))
    )
    (net (code "103") (name "Net-(IC10A-D1)") (class "Default")
      (node (ref "IC10") (pin "14") (pinfunction "D1_14") (pintype "input"))
      (node (ref "IC9") (pin "4") (pinfunction "1Y_4") (pintype "output"))
    )
    (net (code "104") (name "Net-(IC10A-D2)") (class "Default")
      (node (ref "IC10") (pin "13") (pinfunction "D2_13") (pintype "input"))
      (node (ref "IC9") (pin "7") (pinfunction "2Y_7") (pintype "output"))
    )
    (net (code "105") (name "Net-(IC10A-D3)") (class "Default")
      (node (ref "IC10") (pin "12") (pinfunction "D3_12") (pintype "input"))
      (node (ref "IC9") (pin "9") (pinfunction "3Y_9") (pintype "output"))
    )
    (net (code "106") (name "Net-(IC10A-D4)") (class "Default")
      (node (ref "IC10") (pin "11") (pinfunction "D4_11") (pintype "input"))
      (node (ref "IC9") (pin "12") (pinfunction "4Y_12") (pintype "output"))
    )
    (net (code "107") (name "Net-(IC10A-G1)") (class "Default")
      (node (ref "IC10") (pin "10") (pinfunction "G2_10") (pintype "input"))
      (node (ref "IC10") (pin "9") (pinfunction "G1_9") (pintype "input"))
      (node (ref "IC7") (pin "11") (pinfunction "O_11") (pintype "output"))
    )
    (net (code "108") (name "Net-(IC12A-CLK)") (class "Default")
      (node (ref "IC12") (pin "3") (pinfunction "CLK_3") (pintype "input"))
      (node (ref "IC6") (pin "8") (pinfunction "O_8") (pintype "output"))
    )
    (net (code "109") (name "Net-(IC12B-CLK)") (class "Default")
      (node (ref "IC12") (pin "11") (pinfunction "CLK_11") (pintype "input"))
      (node (ref "IC6") (pin "11") (pinfunction "O_11") (pintype "output"))
    )
    (net (code "110") (name "Net-(IC15A-I0)") (class "Default")
      (node (ref "IC15") (pin "1") (pinfunction "I0_1") (pintype "input"))
      (node (ref "IC16") (pin "1") (pinfunction "O_1") (pintype "output"))
    )
    (net (code "111") (name "Net-(IC15A-I1)") (class "Default")
      (node (ref "IC15") (pin "2") (pinfunction "I1_2") (pintype "input"))
      (node (ref "IC16") (pin "4") (pinfunction "O_4") (pintype "output"))
    )
    (net (code "112") (name "Net-(IC15A-I2)") (class "Default")
      (node (ref "IC15") (pin "4") (pinfunction "I2_4") (pintype "input"))
      (node (ref "IC16") (pin "10") (pinfunction "O_10") (pintype "output"))
    )
    (net (code "113") (name "Net-(IC15A-I3)") (class "Default")
      (node (ref "IC15") (pin "5") (pinfunction "I3_5") (pintype "input"))
      (node (ref "IC16") (pin "13") (pinfunction "O_13") (pintype "output"))
    )
    (net (code "114") (name "Net-(IC15A-O)") (class "Default")
      (node (ref "IC15") (pin "6") (pinfunction "O_6") (pintype "output"))
      (node (ref "IC20") (pin "1") (pinfunction "I0_1") (pintype "input"))
      (node (ref "IC3") (pin "11") (pinfunction "2C1_11") (pintype "input"))
    )
    (net (code "115") (name "Net-(IC15B-I0)") (class "Default")
      (node (ref "IC15") (pin "9") (pinfunction "I0_9") (pintype "input"))
      (node (ref "IC17") (pin "1") (pinfunction "O_1") (pintype "output"))
    )
    (net (code "116") (name "Net-(IC15B-I1)") (class "Default")
      (node (ref "IC15") (pin "10") (pinfunction "I1_10") (pintype "input"))
      (node (ref "IC17") (pin "4") (pinfunction "O_4") (pintype "output"))
    )
    (net (code "117") (name "Net-(IC15B-I2)") (class "Default")
      (node (ref "IC15") (pin "12") (pinfunction "I2_12") (pintype "input"))
      (node (ref "IC17") (pin "10") (pinfunction "O_10") (pintype "output"))
    )
    (net (code "118") (name "Net-(IC15B-I3)") (class "Default")
      (node (ref "IC15") (pin "13") (pinfunction "I3_13") (pintype "input"))
      (node (ref "IC17") (pin "13") (pinfunction "O_13") (pintype "output"))
    )
    (net (code "119") (name "Net-(IC15B-O)") (class "Default")
      (node (ref "IC15") (pin "8") (pinfunction "O_8") (pintype "output"))
      (node (ref "IC20") (pin "2") (pinfunction "I1_2") (pintype "input"))
      (node (ref "IC3") (pin "12") (pinfunction "2C2_12") (pintype "input"))
    )
    (net (code "120") (name "Net-(IC18A-O)") (class "Default")
      (node (ref "IC1") (pin "14") (pinfunction "D5_14") (pintype "input"))
      (node (ref "IC1") (pin "15") (pinfunction "D4_15") (pintype "input"))
      (node (ref "IC18") (pin "2") (pinfunction "O_2") (pintype "output"))
    )
    (net (code "121") (name "Net-(IC18B-O)") (class "Default")
      (node (ref "IC1") (pin "13") (pinfunction "D6_13") (pintype "input"))
      (node (ref "IC18") (pin "4") (pinfunction "O_4") (pintype "output"))
    )
    (net (code "122") (name "Net-(IC18D-O)") (class "Default")
      (node (ref "IC18") (pin "8") (pinfunction "O_8") (pintype "output"))
      (node (ref "IC2") (pin "13") (pinfunction "D6_13") (pintype "input"))
      (node (ref "IC2") (pin "3") (pinfunction "D1_3") (pintype "input"))
      (node (ref "IC8") (pin "13") (pinfunction "D6_13") (pintype "input"))
      (node (ref "IC8") (pin "3") (pinfunction "D1_3") (pintype "input"))
    )
    (net (code "123") (name "Net-(IC20A-O)") (class "Default")
      (node (ref "IC20") (pin "3") (pinfunction "O_3") (pintype "output"))
      (node (ref "IC3") (pin "10") (pinfunction "2C0_10") (pintype "input"))
    )
    (net (code "124") (name "OP0") (class "Default")
      (node (ref "IC13") (pin "3") (pinfunction "A2_3") (pintype "input"))
      (node (ref "JP7") (pin "9") (pinfunction "9_9") (pintype "passive"))
    )
    (net (code "125") (name "OP1") (class "Default")
      (node (ref "IC13") (pin "4") (pinfunction "A3_4") (pintype "input"))
      (node (ref "JP7") (pin "8") (pinfunction "8_8") (pintype "passive"))
    )
    (net (code "126") (name "OP2") (class "Default")
      (node (ref "IC13") (pin "5") (pinfunction "A4_5") (pintype "input"))
      (node (ref "JP7") (pin "7") (pinfunction "7_7") (pintype "passive"))
    )
    (net (code "127") (name "OP3") (class "Default")
      (node (ref "IC13") (pin "6") (pinfunction "A5_6") (pintype "input"))
      (node (ref "JP7") (pin "6") (pinfunction "6_6") (pintype "passive"))
    )
    (net (code "128") (name "OP4") (class "Default")
      (node (ref "JP7") (pin "5") (pinfunction "5_5") (pintype "passive"))
    )
    (net (code "129") (name "OP5") (class "Default")
      (node (ref "JP7") (pin "4") (pinfunction "4_4") (pintype "passive"))
    )
    (net (code "130") (name "OP6") (class "Default")
      (node (ref "JP7") (pin "3") (pinfunction "3_3") (pintype "passive"))
    )
    (net (code "131") (name "OP7") (class "Default")
      (node (ref "JP7") (pin "2") (pinfunction "2_2") (pintype "passive"))
    )
    (net (code "132") (name "OP8") (class "Default")
      (node (ref "JP7") (pin "1") (pinfunction "1_1") (pintype "passive"))
    )
    (net (code "133") (name "PROT") (class "Default")
      (node (ref "JP10") (pin "21") (pinfunction "21_21") (pintype "passive"))
    )
    (net (code "134") (name "RBUS0") (class "Default")
      (node (ref "IC13") (pin "18") (pinfunction "Y1_18") (pintype "tri_state"))
      (node (ref "IC5") (pin "18") (pinfunction "Y1_18") (pintype "tri_state"))
      (node (ref "JP4") (pin "1") (pinfunction "1_1") (pintype "passive"))
    )
    (net (code "135") (name "RBUS1") (class "Default")
      (node (ref "IC13") (pin "17") (pinfunction "Y2_17") (pintype "tri_state"))
      (node (ref "IC5") (pin "17") (pinfunction "Y2_17") (pintype "tri_state"))
      (node (ref "JP4") (pin "2") (pinfunction "2_2") (pintype "passive"))
    )
    (net (code "136") (name "RBUS2") (class "Default")
      (node (ref "IC13") (pin "16") (pinfunction "Y3_16") (pintype "tri_state"))
      (node (ref "IC5") (pin "16") (pinfunction "Y3_16") (pintype "tri_state"))
      (node (ref "JP4") (pin "3") (pinfunction "3_3") (pintype "passive"))
    )
    (net (code "137") (name "RBUS3") (class "Default")
      (node (ref "IC13") (pin "15") (pinfunction "Y4_15") (pintype "tri_state"))
      (node (ref "IC5") (pin "15") (pinfunction "Y4_15") (pintype "tri_state"))
      (node (ref "JP4") (pin "4") (pinfunction "4_4") (pintype "passive"))
    )
    (net (code "138") (name "RBUS4") (class "Default")
      (node (ref "IC13") (pin "14") (pinfunction "Y5_14") (pintype "tri_state"))
      (node (ref "IC5") (pin "14") (pinfunction "Y5_14") (pintype "tri_state"))
      (node (ref "JP4") (pin "5") (pinfunction "5_5") (pintype "passive"))
    )
    (net (code "139") (name "RBUS5") (class "Default")
      (node (ref "IC13") (pin "13") (pinfunction "Y6_13") (pintype "tri_state"))
      (node (ref "IC5") (pin "13") (pinfunction "Y6_13") (pintype "tri_state"))
      (node (ref "JP4") (pin "6") (pinfunction "6_6") (pintype "passive"))
    )
    (net (code "140") (name "RBUS6") (class "Default")
      (node (ref "IC13") (pin "12") (pinfunction "Y7_12") (pintype "tri_state"))
      (node (ref "IC5") (pin "12") (pinfunction "Y7_12") (pintype "tri_state"))
      (node (ref "JP4") (pin "7") (pinfunction "7_7") (pintype "passive"))
    )
    (net (code "141") (name "RBUS7") (class "Default")
      (node (ref "IC13") (pin "11") (pinfunction "Y8_11") (pintype "tri_state"))
      (node (ref "IC2") (pin "10") (pinfunction "B_10") (pintype "input"))
      (node (ref "IC5") (pin "11") (pinfunction "Y8_11") (pintype "tri_state"))
      (node (ref "JP4") (pin "8") (pinfunction "8_8") (pintype "passive"))
    )
    (net (code "142") (name "RBUS8") (class "Default")
      (node (ref "IC14") (pin "18") (pinfunction "Y1_18") (pintype "tri_state"))
      (node (ref "JP4") (pin "9") (pinfunction "9_9") (pintype "passive"))
    )
    (net (code "143") (name "RBUS9") (class "Default")
      (node (ref "IC14") (pin "17") (pinfunction "Y2_17") (pintype "tri_state"))
      (node (ref "JP4") (pin "10") (pinfunction "10_10") (pintype "passive"))
    )
    (net (code "144") (name "RBUS10") (class "Default")
      (node (ref "IC14") (pin "16") (pinfunction "Y3_16") (pintype "tri_state"))
      (node (ref "JP4") (pin "11") (pinfunction "11_11") (pintype "passive"))
    )
    (net (code "145") (name "RBUS11") (class "Default")
      (node (ref "IC14") (pin "15") (pinfunction "Y4_15") (pintype "tri_state"))
      (node (ref "JP4") (pin "12") (pinfunction "12_12") (pintype "passive"))
    )
    (net (code "146") (name "RBUS12") (class "Default")
      (node (ref "IC14") (pin "14") (pinfunction "Y5_14") (pintype "tri_state"))
      (node (ref "JP4") (pin "13") (pinfunction "13_13") (pintype "passive"))
    )
    (net (code "147") (name "RBUS13") (class "Default")
      (node (ref "IC14") (pin "13") (pinfunction "Y6_13") (pintype "tri_state"))
      (node (ref "JP4") (pin "14") (pinfunction "14_14") (pintype "passive"))
    )
    (net (code "148") (name "RBUS14") (class "Default")
      (node (ref "IC14") (pin "12") (pinfunction "Y7_12") (pintype "tri_state"))
      (node (ref "JP4") (pin "15") (pinfunction "15_15") (pintype "passive"))
    )
    (net (code "149") (name "RBUS15") (class "Default")
      (node (ref "IC14") (pin "11") (pinfunction "Y8_11") (pintype "tri_state"))
      (node (ref "IC8") (pin "10") (pinfunction "B_10") (pintype "input"))
      (node (ref "JP4") (pin "16") (pinfunction "16_16") (pintype "passive"))
    )
    (net (code "150") (name "RST") (class "Default")
      (node (ref "IC10") (pin "15") (pinfunction "CLR_15") (pintype "input"))
      (node (ref "JP10") (pin "9") (pinfunction "9_9") (pintype "passive"))
    )
    (net (code "151") (name "SP_DIR") (class "Default")
      (node (ref "JP10") (pin "20") (pinfunction "20_20") (pintype "passive"))
    )
    (net (code "152") (name "unconnected-(IC1A-W-Pad6)") (class "Default")
      (node (ref "IC1") (pin "6") (pinfunction "W_6") (pintype "output"))
    )
    (net (code "153") (name "unconnected-(IC2A-W-Pad6)") (class "Default")
      (node (ref "IC2") (pin "6") (pinfunction "W_6") (pintype "output"))
    )
    (net (code "154") (name "unconnected-(IC4A-2Y-Pad9)") (class "Default")
      (node (ref "IC4") (pin "9") (pinfunction "2Y_9") (pintype "output"))
    )
    (net (code "155") (name "unconnected-(IC6A-O-Pad3)") (class "Default")
      (node (ref "IC6") (pin "3") (pinfunction "O_3") (pintype "output"))
    )
    (net (code "156") (name "unconnected-(IC6B-O-Pad6)") (class "Default")
      (node (ref "IC6") (pin "6") (pinfunction "O_6") (pintype "output"))
    )
    (net (code "157") (name "unconnected-(IC8A-W-Pad6)") (class "Default")
      (node (ref "IC8") (pin "6") (pinfunction "W_6") (pintype "output"))
    )
    (net (code "158") (name "unconnected-(IC11A-~{Q}-Pad6)") (class "Default")
      (node (ref "IC11") (pin "6") (pinfunction "~{Q}_6") (pintype "output"))
    )
    (net (code "159") (name "unconnected-(IC11B-~{Q}-Pad8)") (class "Default")
      (node (ref "IC11") (pin "8") (pinfunction "~{Q}_8") (pintype "output"))
    )
    (net (code "160") (name "unconnected-(IC12A-~{Q}-Pad6)") (class "Default")
      (node (ref "IC12") (pin "6") (pinfunction "~{Q}_6") (pintype "output"))
    )
    (net (code "161") (name "unconnected-(IC12B-~{Q}-Pad8)") (class "Default")
      (node (ref "IC12") (pin "8") (pinfunction "~{Q}_8") (pintype "output"))
    )
    (net (code "162") (name "unconnected-(IC18C-O-Pad6)") (class "Default")
      (node (ref "IC18") (pin "6") (pinfunction "O_6") (pintype "output"))
    )
    (net (code "163") (name "unconnected-(IC18E-O-Pad10)") (class "Default")
      (node (ref "IC18") (pin "10") (pinfunction "O_10") (pintype "output"))
    )
    (net (code "164") (name "unconnected-(IC18F-O-Pad12)") (class "Default")
      (node (ref "IC18") (pin "12") (pinfunction "O_12") (pintype "output"))
    )
    (net (code "165") (name "unconnected-(IC20B-O-Pad6)") (class "Default")
      (node (ref "IC20") (pin "6") (pinfunction "O_6") (pintype "output"))
    )
    (net (code "166") (name "unconnected-(IC20C-O-Pad8)") (class "Default")
      (node (ref "IC20") (pin "8") (pinfunction "O_8") (pintype "output"))
    )
    (net (code "167") (name "unconnected-(IC20D-O-Pad11)") (class "Default")
      (node (ref "IC20") (pin "11") (pinfunction "O_11") (pintype "output"))
    )
    (net (code "168") (name "unconnected-(JP9-Pad15)") (class "Default")
      (node (ref "JP9") (pin "15") (pinfunction "15_15") (pintype "passive"))
    )
    (net (code "169") (name "unconnected-(JP9-Pad28)") (class "Default")
      (node (ref "JP9") (pin "28") (pinfunction "28_28") (pintype "passive"))
    )
    (net (code "170") (name "unconnected-(JP9-Pad30)") (class "Default")
      (node (ref "JP9") (pin "30") (pinfunction "30_30") (pintype "passive"))
    )
    (net (code "171") (name "unconnected-(JP9-Pad37)") (class "Default")
      (node (ref "JP9") (pin "37") (pinfunction "37_37") (pintype "passive"))
    )
    (net (code "172") (name "{slash}ALUCARRYIN") (class "Default")
      (node (ref "JP9") (pin "2") (pinfunction "2_2") (pintype "passive"))
    )
    (net (code "173") (name "{slash}ALUHI2MEM") (class "Default")
      (node (ref "JP10") (pin "25") (pinfunction "25_25") (pintype "passive"))
    )
    (net (code "174") (name "{slash}ALULO2MEM") (class "Default")
      (node (ref "JP10") (pin "29") (pinfunction "29_29") (pintype "passive"))
    )
    (net (code "175") (name "{slash}ALUSHR") (class "Default")
      (node (ref "IC1") (pin "9") (pinfunction "C_9") (pintype "input"))
      (node (ref "JP9") (pin "1") (pinfunction "1_1") (pintype "passive"))
    )
    (net (code "176") (name "{slash}BUSIFCEN") (class "Default")
      (node (ref "JP10") (pin "5") (pinfunction "5_5") (pintype "passive"))
    )
    (net (code "177") (name "{slash}CARRY1") (class "Default")
      (node (ref "IC18") (pin "3") (pinfunction "I_3") (pintype "input"))
      (node (ref "JP9") (pin "29") (pinfunction "29_29") (pintype "passive"))
    )
    (net (code "178") (name "{slash}CARRY3") (class "Default")
      (node (ref "IC18") (pin "1") (pinfunction "I_1") (pintype "input"))
      (node (ref "JP9") (pin "31") (pinfunction "31_31") (pintype "passive"))
    )
    (net (code "179") (name "{slash}CNTSP") (class "Default")
      (node (ref "JP10") (pin "3") (pinfunction "3_3") (pintype "passive"))
    )
    (net (code "180") (name "{slash}ENA") (class "Default")
      (node (ref "JP9") (pin "33") (pinfunction "33_33") (pintype "passive"))
    )
    (net (code "181") (name "{slash}ENABUS") (class "Default")
      (node (ref "JP10") (pin "22") (pinfunction "22_22") (pintype "passive"))
    )
    (net (code "182") (name "{slash}ENALU") (class "Default")
      (node (ref "JP9") (pin "39") (pinfunction "39_39") (pintype "passive"))
    )
    (net (code "183") (name "{slash}ENDP") (class "Default")
      (node (ref "JP9") (pin "44") (pinfunction "44_44") (pintype "passive"))
    )
    (net (code "184") (name "{slash}ENIPTR") (class "Default")
      (node (ref "IC13") (pin "1") (pinfunction "G1_1") (pintype "input"))
      (node (ref "IC13") (pin "19") (pinfunction "G2_19") (pintype "input"))
      (node (ref "IC14") (pin "1") (pinfunction "G1_1") (pintype "input"))
      (node (ref "IC14") (pin "19") (pinfunction "G2_19") (pintype "input"))
      (node (ref "JP9") (pin "38") (pinfunction "38_38") (pintype "passive"))
    )
    (net (code "185") (name "{slash}ENLMDR") (class "Default")
      (node (ref "JP9") (pin "34") (pinfunction "34_34") (pintype "passive"))
    )
    (net (code "186") (name "{slash}ENMAR") (class "Default")
      (node (ref "JP9") (pin "48") (pinfunction "48_48") (pintype "passive"))
    )
    (net (code "187") (name "{slash}ENMEM") (class "Default")
      (node (ref "JP10") (pin "16") (pinfunction "16_16") (pintype "passive"))
    )
    (net (code "188") (name "{slash}ENMSW") (class "Default")
      (node (ref "IC5") (pin "1") (pinfunction "G1_1") (pintype "input"))
      (node (ref "IC5") (pin "19") (pinfunction "G2_19") (pintype "input"))
      (node (ref "JP9") (pin "40") (pinfunction "40_40") (pintype "passive"))
    )
    (net (code "189") (name "{slash}ENPC") (class "Default")
      (node (ref "JP9") (pin "42") (pinfunction "42_42") (pintype "passive"))
    )
    (net (code "190") (name "{slash}ENRMDR") (class "Default")
      (node (ref "JP9") (pin "41") (pinfunction "41_41") (pintype "passive"))
    )
    (net (code "191") (name "{slash}ENSP") (class "Default")
      (node (ref "JP9") (pin "46") (pinfunction "46_46") (pintype "passive"))
    )
    (net (code "192") (name "{slash}ENX") (class "Default")
      (node (ref "JP9") (pin "36") (pinfunction "36_36") (pintype "passive"))
    )
    (net (code "193") (name "{slash}ENY") (class "Default")
      (node (ref "JP9") (pin "35") (pinfunction "35_35") (pintype "passive"))
    )
    (net (code "194") (name "{slash}FI") (class "Default")
      (node (ref "IC12") (pin "5") (pinfunction "Q_5") (pintype "output"))
      (node (ref "IC5") (pin "6") (pinfunction "A5_6") (pintype "input"))
      (node (ref "JP10") (pin "32") (pinfunction "32_32") (pintype "passive"))
    )
    (net (code "195") (name "{slash}FP") (class "Default")
      (node (ref "IC11") (pin "9") (pinfunction "Q_9") (pintype "output"))
      (node (ref "IC5") (pin "8") (pinfunction "A7_8") (pintype "input"))
      (node (ref "JP10") (pin "34") (pinfunction "34_34") (pintype "passive"))
    )
    (net (code "196") (name "{slash}FS") (class "Default")
      (node (ref "IC12") (pin "9") (pinfunction "Q_9") (pintype "output"))
      (node (ref "IC5") (pin "7") (pinfunction "A6_7") (pintype "input"))
      (node (ref "JP10") (pin "30") (pinfunction "30_30") (pintype "passive"))
    )
    (net (code "197") (name "{slash}INCPC") (class "Default")
      (node (ref "JP10") (pin "1") (pinfunction "1_1") (pintype "passive"))
    )
    (net (code "198") (name "{slash}INC_MAR") (class "Default")
      (node (ref "JP9") (pin "32") (pinfunction "32_32") (pintype "passive"))
    )
    (net (code "199") (name "{slash}IO") (class "Default")
      (node (ref "JP10") (pin "35") (pinfunction "35_35") (pintype "passive"))
    )
    (net (code "200") (name "{slash}LATCHFLAGS") (class "Default")
      (node (ref "JP10") (pin "12") (pinfunction "12_12") (pintype "passive"))
    )
    (net (code "201") (name "{slash}LATCH_I") (class "Default")
      (node (ref "IC7") (pin "5") (pinfunction "I1_5") (pintype "input"))
      (node (ref "JP9") (pin "47") (pinfunction "47_47") (pintype "passive"))
    )
    (net (code "202") (name "{slash}LATCH_S") (class "Default")
      (node (ref "IC7") (pin "10") (pinfunction "I1_10") (pintype "input"))
      (node (ref "JP9") (pin "45") (pinfunction "45_45") (pintype "passive"))
    )
    (net (code "203") (name "{slash}LDA") (class "Default")
      (node (ref "JP9") (pin "14") (pinfunction "14_14") (pintype "passive"))
    )
    (net (code "204") (name "{slash}LDAHI") (class "Default")
      (node (ref "JP9") (pin "11") (pinfunction "11_11") (pintype "passive"))
    )
    (net (code "205") (name "{slash}LDALO") (class "Default")
      (node (ref "JP9") (pin "12") (pinfunction "12_12") (pintype "passive"))
    )
    (net (code "206") (name "{slash}LDDP") (class "Default")
      (node (ref "JP9") (pin "22") (pinfunction "22_22") (pintype "passive"))
    )
    (net (code "207") (name "{slash}LDMAR") (class "Default")
      (node (ref "JP9") (pin "23") (pinfunction "23_23") (pintype "passive"))
    )
    (net (code "208") (name "{slash}LDMARHI") (class "Default")
      (node (ref "JP9") (pin "17") (pinfunction "17_17") (pintype "passive"))
    )
    (net (code "209") (name "{slash}LDMARLO") (class "Default")
      (node (ref "JP9") (pin "18") (pinfunction "18_18") (pintype "passive"))
    )
    (net (code "210") (name "{slash}LDMDR") (class "Default")
      (node (ref "JP9") (pin "9") (pinfunction "9_9") (pintype "passive"))
    )
    (net (code "211") (name "{slash}LDMDRHI") (class "Default")
      (node (ref "JP9") (pin "10") (pinfunction "10_10") (pintype "passive"))
    )
    (net (code "212") (name "{slash}LDMDRLO") (class "Default")
      (node (ref "JP9") (pin "7") (pinfunction "7_7") (pintype "passive"))
    )
    (net (code "213") (name "{slash}LDMEM") (class "Default")
      (node (ref "JP10") (pin "15") (pinfunction "15_15") (pintype "passive"))
    )
    (net (code "214") (name "{slash}LDMSW") (class "Default")
      (node (ref "IC11") (pin "11") (pinfunction "CLK_11") (pintype "input"))
      (node (ref "IC11") (pin "3") (pinfunction "CLK_3") (pintype "input"))
      (node (ref "IC7") (pin "13") (pinfunction "I1_13") (pintype "input"))
      (node (ref "IC7") (pin "4") (pinfunction "I0_4") (pintype "input"))
      (node (ref "IC7") (pin "9") (pinfunction "I0_9") (pintype "input"))
      (node (ref "IC9") (pin "1") (pinfunction "~{A}/B_1") (pintype "input"))
      (node (ref "JP9") (pin "20") (pinfunction "20_20") (pintype "passive"))
    )
    (net (code "215") (name "{slash}LDPC") (class "Default")
      (node (ref "JP9") (pin "19") (pinfunction "19_19") (pintype "passive"))
    )
    (net (code "216") (name "{slash}LDSP") (class "Default")
      (node (ref "JP9") (pin "21") (pinfunction "21_21") (pintype "passive"))
    )
    (net (code "217") (name "{slash}LDX") (class "Default")
      (node (ref "JP9") (pin "13") (pinfunction "13_13") (pintype "passive"))
    )
    (net (code "218") (name "{slash}LDY") (class "Default")
      (node (ref "JP9") (pin "16") (pinfunction "16_16") (pintype "passive"))
    )
    (net (code "219") (name "{slash}LOAD_IR") (class "Default")
      (node (ref "JP10") (pin "26") (pinfunction "26_26") (pintype "passive"))
    )
    (net (code "220") (name "{slash}MEM2ALUHI") (class "Default")
      (node (ref "JP10") (pin "27") (pinfunction "27_27") (pintype "passive"))
    )
    (net (code "221") (name "{slash}MEM2ALULO") (class "Default")
      (node (ref "JP10") (pin "31") (pinfunction "31_31") (pintype "passive"))
    )
    (net (code "222") (name "{slash}MEMOP") (class "Default")
      (node (ref "JP10") (pin "11") (pinfunction "11_11") (pintype "passive"))
    )
    (net (code "223") (name "{slash}NP_FAULT") (class "Default")
      (node (ref "JP10") (pin "36") (pinfunction "36_36") (pintype "passive"))
    )
    (net (code "224") (name "{slash}RST") (class "Default")
      (node (ref "IC11") (pin "10") (pinfunction "PRE_10") (pintype "input"))
      (node (ref "IC12") (pin "13") (pinfunction "CLR_13") (pintype "input"))
      (node (ref "IC12") (pin "4") (pinfunction "PRE_4") (pintype "input"))
      (node (ref "JP10") (pin "7") (pinfunction "7_7") (pintype "passive"))
    )
    (net (code "225") (name "{slash}WR_FAULT") (class "Default")
      (node (ref "JP10") (pin "33") (pinfunction "33_33") (pintype "passive"))
    )
  )
)
